# HAT_ID01_OLED.net
KiCad netlist of a schematic drawn in Altium Designer
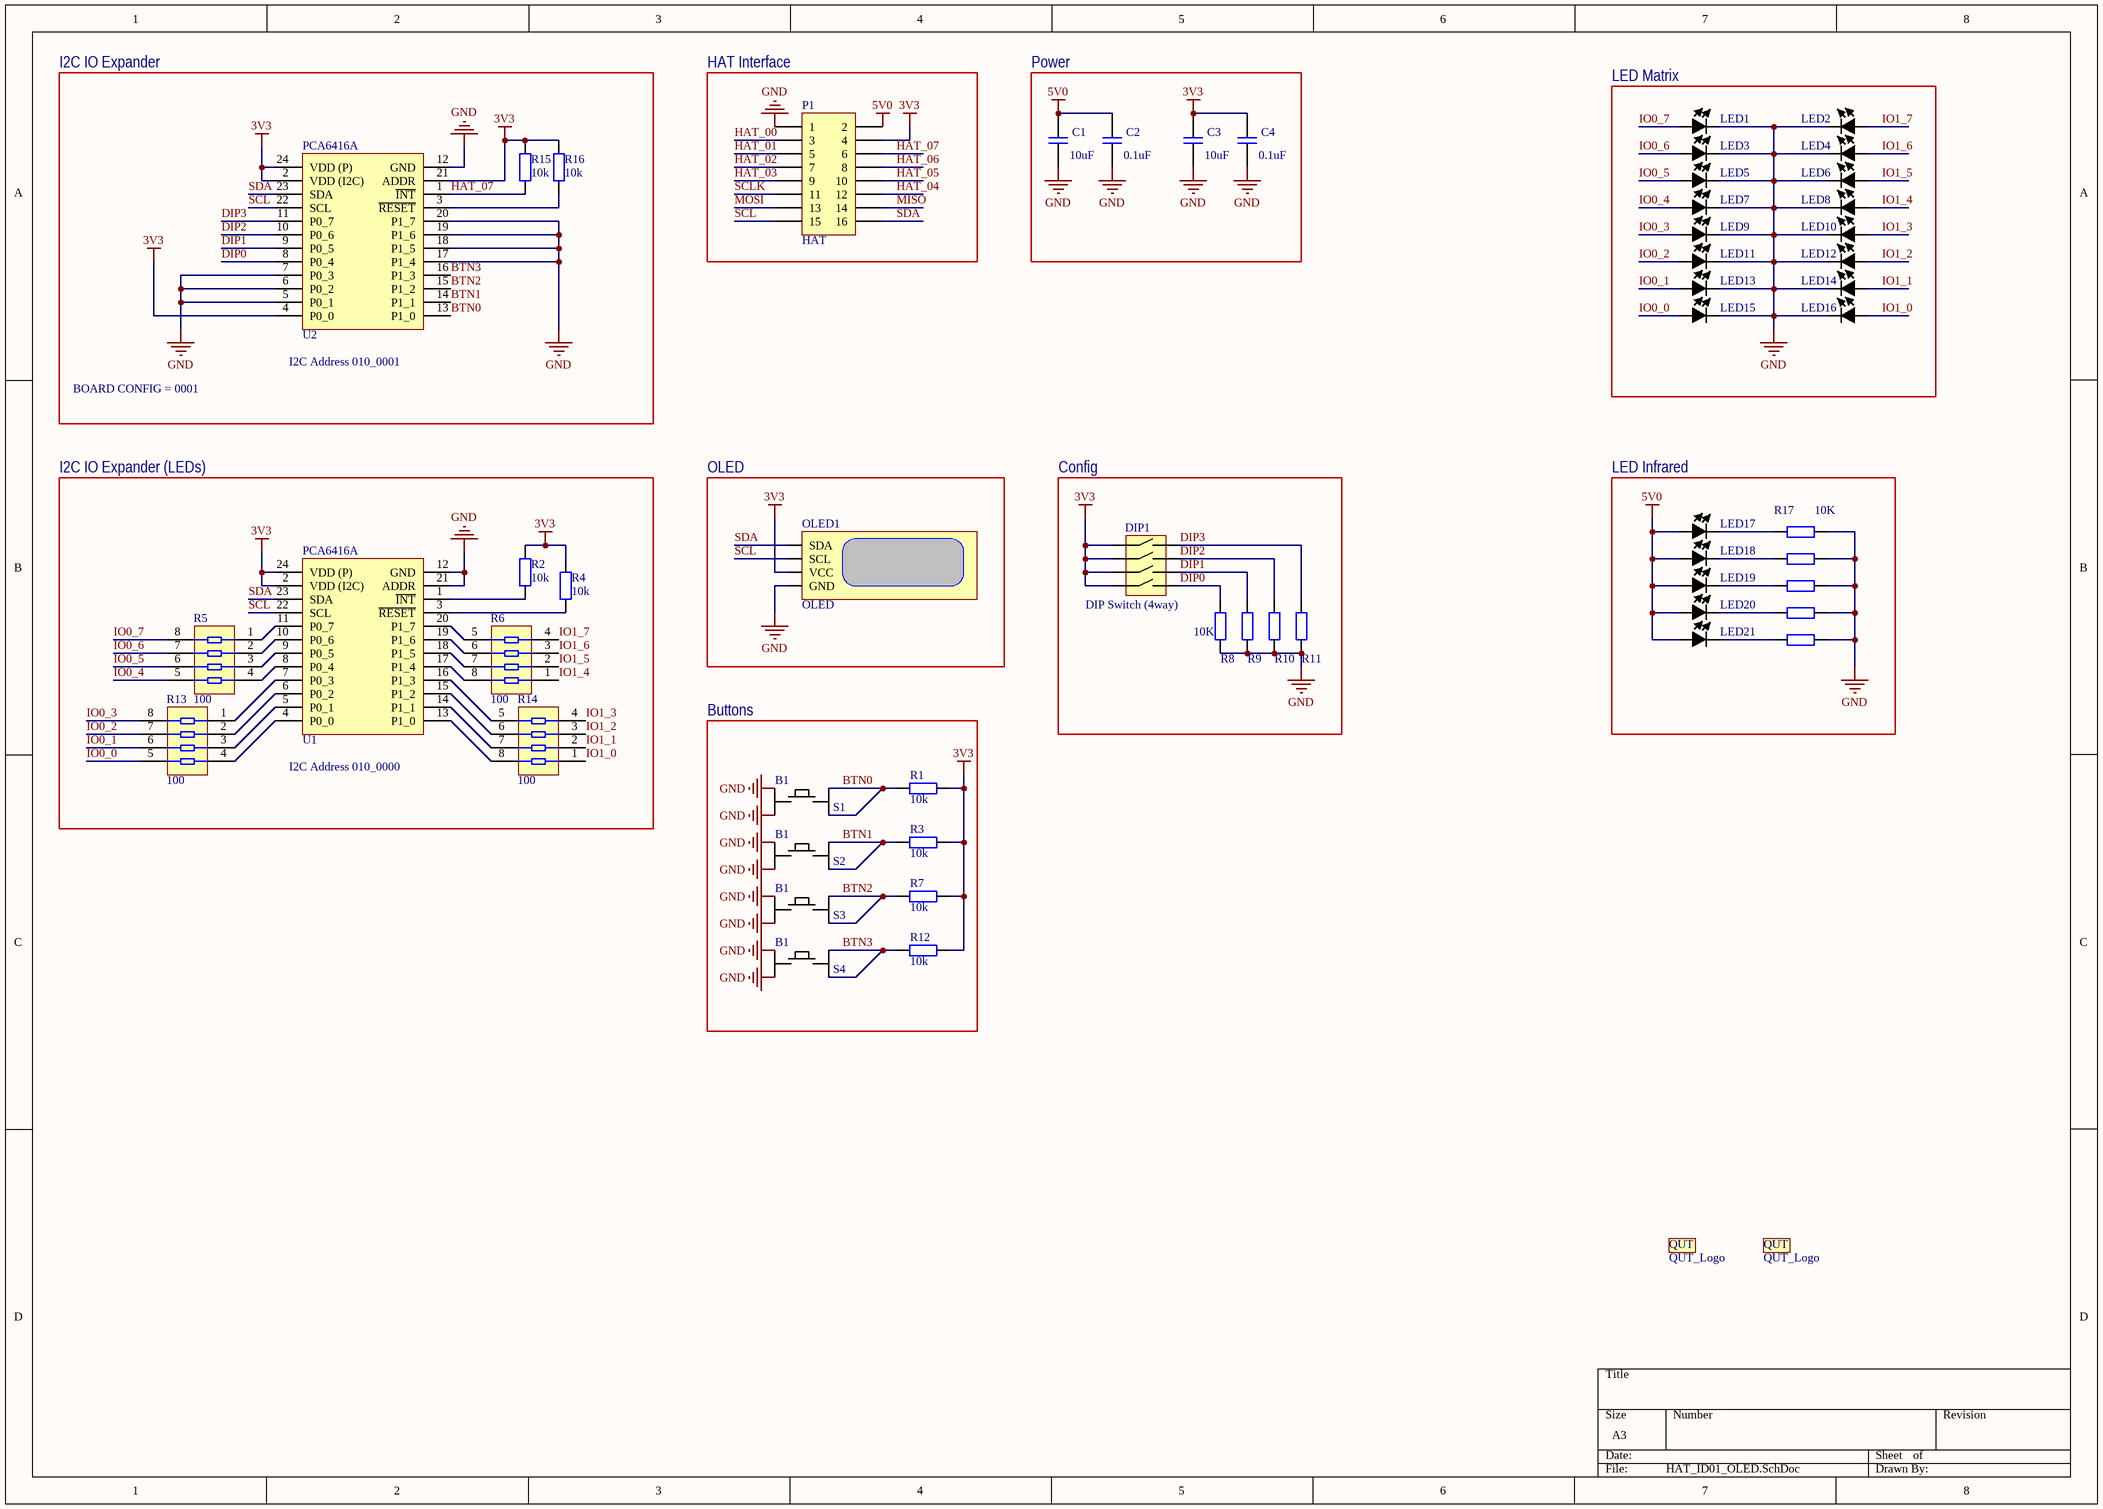
[diagram p0: HAT_ID01_OLED.SchDoc]

(export (version "E")
  (design (tool "Eeschema 10.0.6"))
  (components
    (comp (ref "C1")
      (value "10uF")
      (footprint "C0805")
      (description "Surface mount capacitor")
      (fields (field (name "Comment") "CAP SMD"))
      (libsource (lib "Penguin") (part "CAP SMD"))
    )
    (comp (ref "C2")
      (value "0.1uF")
      (footprint "C0805")
      (description "Surface mount capacitor")
      (fields (field (name "Comment") "CAP SMD"))
      (libsource (lib "Penguin") (part "CAP SMD"))
    )
    (comp (ref "C3")
      (value "10uF")
      (footprint "C0805")
      (description "Surface mount capacitor")
      (fields (field (name "Comment") "CAP SMD"))
      (libsource (lib "Penguin") (part "CAP SMD"))
    )
    (comp (ref "C4")
      (value "0.1uF")
      (footprint "C0805")
      (description "Surface mount capacitor")
      (fields (field (name "Comment") "CAP SMD"))
      (libsource (lib "Penguin") (part "CAP SMD"))
    )
    (comp (ref "DIP1")
      (value "DIP Switch (4way)")
      (footprint "DIP SMD")
      (libsource (lib "QUT") (part "DIP Switch (4way)"))
    )
    (comp (ref "LED1") (value "LED*") (footprint "C0805") (libsource (lib "QUT") (part "LED")))
    (comp (ref "LED2") (value "LED*") (footprint "C0805") (libsource (lib "QUT") (part "LED")))
    (comp (ref "LED3") (value "LED*") (footprint "C0805") (libsource (lib "QUT") (part "LED")))
    (comp (ref "LED4") (value "LED*") (footprint "C0805") (libsource (lib "QUT") (part "LED")))
    (comp (ref "LED5") (value "LED*") (footprint "C0805") (libsource (lib "QUT") (part "LED")))
    (comp (ref "LED6") (value "LED*") (footprint "C0805") (libsource (lib "QUT") (part "LED")))
    (comp (ref "LED7") (value "LED*") (footprint "C0805") (libsource (lib "QUT") (part "LED")))
    (comp (ref "LED8") (value "LED*") (footprint "C0805") (libsource (lib "QUT") (part "LED")))
    (comp (ref "LED9") (value "LED*") (footprint "C0805") (libsource (lib "QUT") (part "LED")))
    (comp (ref "LED10") (value "LED*") (footprint "C0805") (libsource (lib "QUT") (part "LED")))
    (comp (ref "LED11") (value "LED*") (footprint "C0805") (libsource (lib "QUT") (part "LED")))
    (comp (ref "LED12") (value "LED*") (footprint "C0805") (libsource (lib "QUT") (part "LED")))
    (comp (ref "LED13") (value "LED*") (footprint "C0805") (libsource (lib "QUT") (part "LED")))
    (comp (ref "LED14") (value "LED*") (footprint "C0805") (libsource (lib "QUT") (part "LED")))
    (comp (ref "LED15") (value "LED*") (footprint "C0805") (libsource (lib "QUT") (part "LED")))
    (comp (ref "LED16") (value "LED*") (footprint "C0805") (libsource (lib "QUT") (part "LED")))
    (comp (ref "LED17") (value "LED*") (footprint "C0805") (libsource (lib "QUT") (part "LED")))
    (comp (ref "LED18") (value "LED*") (footprint "C0805") (libsource (lib "QUT") (part "LED")))
    (comp (ref "LED19") (value "LED*") (footprint "C0805") (libsource (lib "QUT") (part "LED")))
    (comp (ref "LED20") (value "LED*") (footprint "C0805") (libsource (lib "QUT") (part "LED")))
    (comp (ref "LED21") (value "LED*") (footprint "C0805") (libsource (lib "QUT") (part "LED")))
    (comp (ref "LG1") (value "QUT_Logo") (footprint "QUT_Logo") (libsource (lib "Penguin") (part "QUT_Logo")))
    (comp (ref "LG2") (value "QUT_Logo") (footprint "QUT_Logo") (libsource (lib "Penguin") (part "QUT_Logo")))
    (comp (ref "OLED1") (value "OLED") (footprint "OLED") (libsource (lib "PenguinPi_v2") (part "OLED")))
    (comp (ref "P1")
      (value "HAT")
      (footprint "HDR2X8")
      (description "Header, 8-Pin, Dual row")
      (fields (field (name "PUBLISHER") "Altium Limited"))
      (libsource (lib "Miscellaneous Connectors") (part "Header 8X2"))
    )
    (comp (ref "R1")
      (value "10k")
      (footprint "RESC2012X07N")
      (description "0805 surface mount resistor")
      (fields (field (name "Comment") "RES SMD"))
      (libsource (lib "") (part "RES SMD_1"))
    )
    (comp (ref "R2")
      (value "10k")
      (footprint "RESC2012X07N")
      (description "0805 surface mount resistor")
      (fields (field (name "Comment") "RES SMD"))
      (libsource (lib "Penguin") (part "RES SMD"))
    )
    (comp (ref "R3")
      (value "10k")
      (footprint "RESC2012X07N")
      (description "0805 surface mount resistor")
      (fields (field (name "Comment") "RES SMD"))
      (libsource (lib "") (part "RES SMD_1"))
    )
    (comp (ref "R4")
      (value "10k")
      (footprint "RESC2012X07N")
      (description "0805 surface mount resistor")
      (fields (field (name "Comment") "RES SMD"))
      (libsource (lib "Penguin") (part "RES SMD"))
    )
    (comp (ref "R5")
      (value "100")
      (footprint "CAC-80P319X155-8M")
      (description "Surface mount resistor array")
      (fields (field (name "Comment") "ARRAY"))
      (libsource (lib "Penguin") (part "RES-ARRAY"))
    )
    (comp (ref "R6")
      (value "100")
      (footprint "CAC-80P319X155-8M")
      (description "Surface mount resistor array")
      (fields (field (name "Comment") "ARRAY"))
      (libsource (lib "") (part "RES-ARRAY_1"))
    )
    (comp (ref "R7")
      (value "10k")
      (footprint "RESC2012X07N")
      (description "0805 surface mount resistor")
      (fields (field (name "Comment") "RES SMD"))
      (libsource (lib "") (part "RES SMD_1"))
    )
    (comp (ref "R8")
      (value "10K")
      (footprint "RESC2012X07N")
      (description "0805 surface mount resistor")
      (fields (field (name "Comment") "RES SMD"))
      (libsource (lib "Penguin") (part "RES SMD"))
    )
    (comp (ref "R9")
      (value "RES SMD")
      (footprint "RESC2012X07N")
      (description "0805 surface mount resistor")
      (libsource (lib "Penguin") (part "RES SMD"))
    )
    (comp (ref "R10")
      (value "RES SMD")
      (footprint "RESC2012X07N")
      (description "0805 surface mount resistor")
      (libsource (lib "Penguin") (part "RES SMD"))
    )
    (comp (ref "R11")
      (value "RES SMD")
      (footprint "RESC2012X07N")
      (description "0805 surface mount resistor")
      (libsource (lib "Penguin") (part "RES SMD"))
    )
    (comp (ref "R12")
      (value "10k")
      (footprint "RESC2012X07N")
      (description "0805 surface mount resistor")
      (fields (field (name "Comment") "RES SMD"))
      (libsource (lib "") (part "RES SMD_1"))
    )
    (comp (ref "R13")
      (value "100")
      (footprint "CAC-80P319X155-8M")
      (description "Surface mount resistor array")
      (fields (field (name "Comment") "ARRAY"))
      (libsource (lib "Penguin") (part "RES-ARRAY"))
    )
    (comp (ref "R14")
      (value "100")
      (footprint "CAC-80P319X155-8M")
      (description "Surface mount resistor array")
      (fields (field (name "Comment") "ARRAY"))
      (libsource (lib "") (part "RES-ARRAY_1"))
    )
    (comp (ref "R15")
      (value "10k")
      (footprint "RESC2012X07N")
      (description "0805 surface mount resistor")
      (fields (field (name "Comment") "RES SMD"))
      (libsource (lib "Penguin") (part "RES SMD"))
    )
    (comp (ref "R16")
      (value "10k")
      (footprint "RESC2012X07N")
      (description "0805 surface mount resistor")
      (fields (field (name "Comment") "RES SMD"))
      (libsource (lib "Penguin") (part "RES SMD"))
    )
    (comp (ref "R17")
      (value "10K")
      (footprint "RESC2012X07N")
      (description "0805 surface mount resistor")
      (fields (field (name "Comment") "RES SMD"))
      (libsource (lib "") (part "RES SMD_1"))
    )
    (comp (ref "R18")
      (value "RES SMD")
      (footprint "RESC2012X07N")
      (description "0805 surface mount resistor")
      (libsource (lib "") (part "RES SMD_1"))
    )
    (comp (ref "R19")
      (value "RES SMD")
      (footprint "RESC2012X07N")
      (description "0805 surface mount resistor")
      (libsource (lib "") (part "RES SMD_1"))
    )
    (comp (ref "R20")
      (value "RES SMD")
      (footprint "RESC2012X07N")
      (description "0805 surface mount resistor")
      (libsource (lib "") (part "RES SMD_1"))
    )
    (comp (ref "R21")
      (value "RES SMD")
      (footprint "RESC2012X07N")
      (description "0805 surface mount resistor")
      (libsource (lib "") (part "RES SMD_1"))
    )
    (comp (ref "S1")
      (value "B1")
      (footprint "E-SWITCH-TL3342")
      (description "TL 3342 surface mount pushbutton")
      (libsource (lib "Penguin") (part "E-SWITCH-PUSHBUTTON"))
    )
    (comp (ref "S2")
      (value "B1")
      (footprint "E-SWITCH-TL3342")
      (description "TL 3342 surface mount pushbutton")
      (libsource (lib "Penguin") (part "E-SWITCH-PUSHBUTTON"))
    )
    (comp (ref "S3")
      (value "B1")
      (footprint "E-SWITCH-TL3342")
      (description "TL 3342 surface mount pushbutton")
      (libsource (lib "Penguin") (part "E-SWITCH-PUSHBUTTON"))
    )
    (comp (ref "S4")
      (value "B1")
      (footprint "E-SWITCH-TL3342")
      (description "TL 3342 surface mount pushbutton")
      (libsource (lib "Penguin") (part "E-SWITCH-PUSHBUTTON"))
    )
    (comp (ref "U1")
      (value "PCA6416A")
      (footprint "TSOP65P640X110-24N")
      (description "Low-voltage translating 16-bit I2C I/O port expander")
      (libsource (lib "Penguin") (part "PCA6416APW"))
    )
    (comp (ref "U2")
      (value "PCA6416A")
      (footprint "TSOP65P640X110-24N")
      (description "Low-voltage translating 16-bit I2C I/O port expander")
      (libsource (lib "Penguin") (part "PCA6416APW"))
    )
  )
  (nets
    (net (code "1") (name "/BTN0") (class "Default")
      (node (ref "R1") (pin "2") (pinfunction "2_2") (pintype "passive"))
      (node (ref "S1") (pin "3") (pinfunction "B'_3") (pintype "passive"))
      (node (ref "S1") (pin "4") (pinfunction "B_4") (pintype "passive"))
      (node (ref "U2") (pin "13") (pinfunction "P1_0_13") (pintype "passive"))
    )
    (net (code "2") (name "/BTN1") (class "Default")
      (node (ref "R3") (pin "2") (pinfunction "2_2") (pintype "passive"))
      (node (ref "S2") (pin "3") (pinfunction "B'_3") (pintype "passive"))
      (node (ref "S2") (pin "4") (pinfunction "B_4") (pintype "passive"))
      (node (ref "U2") (pin "14") (pinfunction "P1_1_14") (pintype "passive"))
    )
    (net (code "3") (name "/BTN2") (class "Default")
      (node (ref "R7") (pin "2") (pinfunction "2_2") (pintype "passive"))
      (node (ref "S3") (pin "3") (pinfunction "B'_3") (pintype "passive"))
      (node (ref "S3") (pin "4") (pinfunction "B_4") (pintype "passive"))
      (node (ref "U2") (pin "15") (pinfunction "P1_2_15") (pintype "passive"))
    )
    (net (code "4") (name "/BTN3") (class "Default")
      (node (ref "R12") (pin "2") (pinfunction "2_2") (pintype "passive"))
      (node (ref "S4") (pin "3") (pinfunction "B'_3") (pintype "passive"))
      (node (ref "S4") (pin "4") (pinfunction "B_4") (pintype "passive"))
      (node (ref "U2") (pin "16") (pinfunction "P1_3_16") (pintype "passive"))
    )
    (net (code "5") (name "/DIP0") (class "Default")
      (node (ref "DIP1") (pin "4") (pinfunction "4_4") (pintype "passive"))
      (node (ref "R8") (pin "2") (pinfunction "2_2") (pintype "passive"))
      (node (ref "U2") (pin "8") (pinfunction "P0_4_8") (pintype "passive"))
    )
    (net (code "6") (name "/DIP1") (class "Default")
      (node (ref "DIP1") (pin "5") (pinfunction "5_5") (pintype "passive"))
      (node (ref "R9") (pin "2") (pinfunction "2_2") (pintype "passive"))
      (node (ref "U2") (pin "9") (pinfunction "P0_5_9") (pintype "passive"))
    )
    (net (code "7") (name "/DIP2") (class "Default")
      (node (ref "DIP1") (pin "6") (pinfunction "6_6") (pintype "passive"))
      (node (ref "R10") (pin "2") (pinfunction "2_2") (pintype "passive"))
      (node (ref "U2") (pin "10") (pinfunction "P0_6_10") (pintype "passive"))
    )
    (net (code "8") (name "/DIP3") (class "Default")
      (node (ref "DIP1") (pin "7") (pinfunction "7_7") (pintype "passive"))
      (node (ref "R11") (pin "2") (pinfunction "2_2") (pintype "passive"))
      (node (ref "U2") (pin "11") (pinfunction "P0_7_11") (pintype "passive"))
    )
    (net (code "9") (name "/HAT_00") (class "Default")
      (node (ref "P1") (pin "3") (pinfunction "3_3") (pintype "passive"))
    )
    (net (code "10") (name "/HAT_01") (class "Default")
      (node (ref "P1") (pin "5") (pinfunction "5_5") (pintype "passive"))
    )
    (net (code "11") (name "/HAT_02") (class "Default")
      (node (ref "P1") (pin "7") (pinfunction "7_7") (pintype "passive"))
    )
    (net (code "12") (name "/HAT_03") (class "Default")
      (node (ref "P1") (pin "9") (pinfunction "9_9") (pintype "passive"))
    )
    (net (code "13") (name "/HAT_04") (class "Default")
      (node (ref "P1") (pin "12") (pinfunction "12_12") (pintype "passive"))
    )
    (net (code "14") (name "/HAT_05") (class "Default")
      (node (ref "P1") (pin "10") (pinfunction "10_10") (pintype "passive"))
    )
    (net (code "15") (name "/HAT_06") (class "Default")
      (node (ref "P1") (pin "8") (pinfunction "8_8") (pintype "passive"))
    )
    (net (code "16") (name "/HAT_07") (class "Default")
      (node (ref "P1") (pin "6") (pinfunction "6_6") (pintype "passive"))
      (node (ref "R15") (pin "1") (pinfunction "1_1") (pintype "passive"))
      (node (ref "U2") (pin "1") (pinfunction "~{INT}_1") (pintype "passive"))
    )
    (net (code "17") (name "/IO0_0") (class "Default")
      (node (ref "LED15") (pin "1") (pinfunction "1_1") (pintype "passive"))
      (node (ref "R13") (pin "5") (pintype "passive"))
    )
    (net (code "18") (name "/IO0_1") (class "Default")
      (node (ref "LED13") (pin "1") (pinfunction "1_1") (pintype "passive"))
      (node (ref "R13") (pin "6") (pintype "passive"))
    )
    (net (code "19") (name "/IO0_2") (class "Default")
      (node (ref "LED11") (pin "1") (pinfunction "1_1") (pintype "passive"))
      (node (ref "R13") (pin "7") (pintype "passive"))
    )
    (net (code "20") (name "/IO0_3") (class "Default")
      (node (ref "LED9") (pin "1") (pinfunction "1_1") (pintype "passive"))
      (node (ref "R13") (pin "8") (pintype "passive"))
    )
    (net (code "21") (name "/IO0_4") (class "Default")
      (node (ref "LED7") (pin "1") (pinfunction "1_1") (pintype "passive"))
      (node (ref "R5") (pin "5") (pintype "passive"))
    )
    (net (code "22") (name "/IO0_5") (class "Default")
      (node (ref "LED5") (pin "1") (pinfunction "1_1") (pintype "passive"))
      (node (ref "R5") (pin "6") (pintype "passive"))
    )
    (net (code "23") (name "/IO0_6") (class "Default")
      (node (ref "LED3") (pin "1") (pinfunction "1_1") (pintype "passive"))
      (node (ref "R5") (pin "7") (pintype "passive"))
    )
    (net (code "24") (name "/IO0_7") (class "Default")
      (node (ref "LED1") (pin "1") (pinfunction "1_1") (pintype "passive"))
      (node (ref "R5") (pin "8") (pintype "passive"))
    )
    (net (code "25") (name "/IO1_0") (class "Default")
      (node (ref "LED16") (pin "1") (pinfunction "1_1") (pintype "passive"))
      (node (ref "R14") (pin "1") (pintype "passive"))
    )
    (net (code "26") (name "/IO1_1") (class "Default")
      (node (ref "LED14") (pin "1") (pinfunction "1_1") (pintype "passive"))
      (node (ref "R14") (pin "2") (pintype "passive"))
    )
    (net (code "27") (name "/IO1_2") (class "Default")
      (node (ref "LED12") (pin "1") (pinfunction "1_1") (pintype "passive"))
      (node (ref "R14") (pin "3") (pintype "passive"))
    )
    (net (code "28") (name "/IO1_3") (class "Default")
      (node (ref "LED10") (pin "1") (pinfunction "1_1") (pintype "passive"))
      (node (ref "R14") (pin "4") (pintype "passive"))
    )
    (net (code "29") (name "/IO1_4") (class "Default")
      (node (ref "LED8") (pin "1") (pinfunction "1_1") (pintype "passive"))
      (node (ref "R6") (pin "1") (pintype "passive"))
    )
    (net (code "30") (name "/IO1_5") (class "Default")
      (node (ref "LED6") (pin "1") (pinfunction "1_1") (pintype "passive"))
      (node (ref "R6") (pin "2") (pintype "passive"))
    )
    (net (code "31") (name "/IO1_6") (class "Default")
      (node (ref "LED4") (pin "1") (pinfunction "1_1") (pintype "passive"))
      (node (ref "R6") (pin "3") (pintype "passive"))
    )
    (net (code "32") (name "/IO1_7") (class "Default")
      (node (ref "LED2") (pin "1") (pinfunction "1_1") (pintype "passive"))
      (node (ref "R6") (pin "4") (pintype "passive"))
    )
    (net (code "33") (name "/MISO") (class "Default")
      (node (ref "P1") (pin "14") (pinfunction "14_14") (pintype "passive"))
    )
    (net (code "34") (name "/MOSI") (class "Default")
      (node (ref "P1") (pin "13") (pinfunction "13_13") (pintype "passive"))
    )
    (net (code "35") (name "/SCL") (class "Default")
      (node (ref "OLED1") (pin "3") (pinfunction "SCL_3") (pintype "passive"))
      (node (ref "P1") (pin "15") (pinfunction "15_15") (pintype "passive"))
      (node (ref "U1") (pin "22") (pinfunction "SCL_22") (pintype "passive"))
      (node (ref "U2") (pin "22") (pinfunction "SCL_22") (pintype "passive"))
    )
    (net (code "36") (name "/SCLK") (class "Default")
      (node (ref "P1") (pin "11") (pinfunction "11_11") (pintype "passive"))
    )
    (net (code "37") (name "/SDA") (class "Default")
      (node (ref "OLED1") (pin "4") (pinfunction "SDA_4") (pintype "passive"))
      (node (ref "P1") (pin "16") (pinfunction "16_16") (pintype "passive"))
      (node (ref "U1") (pin "23") (pinfunction "SDA_23") (pintype "passive"))
      (node (ref "U2") (pin "23") (pinfunction "SDA_23") (pintype "passive"))
    )
    (net (code "38") (name "3V3") (class "Default")
      (node (ref "C3") (pin "2") (pinfunction "K_2") (pintype "passive"))
      (node (ref "C4") (pin "2") (pinfunction "K_2") (pintype "passive"))
      (node (ref "DIP1") (pin "0") (pinfunction "0_0") (pintype "passive"))
      (node (ref "DIP1") (pin "1") (pinfunction "1_1") (pintype "passive"))
      (node (ref "DIP1") (pin "2") (pinfunction "2_2") (pintype "passive"))
      (node (ref "DIP1") (pin "3") (pinfunction "3_3") (pintype "passive"))
      (node (ref "OLED1") (pin "2") (pinfunction "VCC_2") (pintype "passive"))
      (node (ref "P1") (pin "4") (pinfunction "4_4") (pintype "passive"))
      (node (ref "R1") (pin "1") (pinfunction "1_1") (pintype "passive"))
      (node (ref "R12") (pin "1") (pinfunction "1_1") (pintype "passive"))
      (node (ref "R15") (pin "2") (pinfunction "2_2") (pintype "passive"))
      (node (ref "R16") (pin "2") (pinfunction "2_2") (pintype "passive"))
      (node (ref "R2") (pin "2") (pinfunction "2_2") (pintype "passive"))
      (node (ref "R3") (pin "1") (pinfunction "1_1") (pintype "passive"))
      (node (ref "R4") (pin "2") (pinfunction "2_2") (pintype "passive"))
      (node (ref "R7") (pin "1") (pinfunction "1_1") (pintype "passive"))
      (node (ref "U1") (pin "2") (pinfunction "VDD_(I2C)_2") (pintype "passive"))
      (node (ref "U1") (pin "24") (pinfunction "VDD_(P)_24") (pintype "passive"))
      (node (ref "U2") (pin "2") (pinfunction "VDD_(I2C)_2") (pintype "passive"))
      (node (ref "U2") (pin "21") (pinfunction "ADDR_21") (pintype "passive"))
      (node (ref "U2") (pin "24") (pinfunction "VDD_(P)_24") (pintype "passive"))
      (node (ref "U2") (pin "4") (pinfunction "P0_0_4") (pintype "passive"))
    )
    (net (code "39") (name "5V0") (class "Default")
      (node (ref "C1") (pin "2") (pinfunction "K_2") (pintype "passive"))
      (node (ref "C2") (pin "2") (pinfunction "K_2") (pintype "passive"))
      (node (ref "LED17") (pin "1") (pinfunction "1_1") (pintype "passive"))
      (node (ref "LED18") (pin "1") (pinfunction "1_1") (pintype "passive"))
      (node (ref "LED19") (pin "1") (pinfunction "1_1") (pintype "passive"))
      (node (ref "LED20") (pin "1") (pinfunction "1_1") (pintype "passive"))
      (node (ref "LED21") (pin "1") (pinfunction "1_1") (pintype "passive"))
      (node (ref "P1") (pin "2") (pinfunction "2_2") (pintype "passive"))
    )
    (net (code "40") (name "GND") (class "Default")
      (node (ref "C1") (pin "1") (pinfunction "A_1") (pintype "passive"))
      (node (ref "C2") (pin "1") (pinfunction "A_1") (pintype "passive"))
      (node (ref "C3") (pin "1") (pinfunction "A_1") (pintype "passive"))
      (node (ref "C4") (pin "1") (pinfunction "A_1") (pintype "passive"))
      (node (ref "LED1") (pin "2") (pinfunction "2_2") (pintype "passive"))
      (node (ref "LED10") (pin "2") (pinfunction "2_2") (pintype "passive"))
      (node (ref "LED11") (pin "2") (pinfunction "2_2") (pintype "passive"))
      (node (ref "LED12") (pin "2") (pinfunction "2_2") (pintype "passive"))
      (node (ref "LED13") (pin "2") (pinfunction "2_2") (pintype "passive"))
      (node (ref "LED14") (pin "2") (pinfunction "2_2") (pintype "passive"))
      (node (ref "LED15") (pin "2") (pinfunction "2_2") (pintype "passive"))
      (node (ref "LED16") (pin "2") (pinfunction "2_2") (pintype "passive"))
      (node (ref "LED2") (pin "2") (pinfunction "2_2") (pintype "passive"))
      (node (ref "LED3") (pin "2") (pinfunction "2_2") (pintype "passive"))
      (node (ref "LED4") (pin "2") (pinfunction "2_2") (pintype "passive"))
      (node (ref "LED5") (pin "2") (pinfunction "2_2") (pintype "passive"))
      (node (ref "LED6") (pin "2") (pinfunction "2_2") (pintype "passive"))
      (node (ref "LED7") (pin "2") (pinfunction "2_2") (pintype "passive"))
      (node (ref "LED8") (pin "2") (pinfunction "2_2") (pintype "passive"))
      (node (ref "LED9") (pin "2") (pinfunction "2_2") (pintype "passive"))
      (node (ref "OLED1") (pin "1") (pinfunction "GND_1") (pintype "passive"))
      (node (ref "P1") (pin "1") (pinfunction "1_1") (pintype "passive"))
      (node (ref "R10") (pin "1") (pinfunction "1_1") (pintype "passive"))
      (node (ref "R11") (pin "1") (pinfunction "1_1") (pintype "passive"))
      (node (ref "R17") (pin "1") (pinfunction "1_1") (pintype "passive"))
      (node (ref "R18") (pin "1") (pinfunction "1_1") (pintype "passive"))
      (node (ref "R19") (pin "1") (pinfunction "1_1") (pintype "passive"))
      (node (ref "R20") (pin "1") (pinfunction "1_1") (pintype "passive"))
      (node (ref "R21") (pin "1") (pinfunction "1_1") (pintype "passive"))
      (node (ref "R8") (pin "1") (pinfunction "1_1") (pintype "passive"))
      (node (ref "R9") (pin "1") (pinfunction "1_1") (pintype "passive"))
      (node (ref "S1") (pin "1") (pinfunction "A_1") (pintype "passive"))
      (node (ref "S1") (pin "2") (pinfunction "A'_2") (pintype "passive"))
      (node (ref "S2") (pin "1") (pinfunction "A_1") (pintype "passive"))
      (node (ref "S2") (pin "2") (pinfunction "A'_2") (pintype "passive"))
      (node (ref "S3") (pin "1") (pinfunction "A_1") (pintype "passive"))
      (node (ref "S3") (pin "2") (pinfunction "A'_2") (pintype "passive"))
      (node (ref "S4") (pin "1") (pinfunction "A_1") (pintype "passive"))
      (node (ref "S4") (pin "2") (pinfunction "A'_2") (pintype "passive"))
      (node (ref "U1") (pin "12") (pinfunction "GND_12") (pintype "passive"))
      (node (ref "U1") (pin "21") (pinfunction "ADDR_21") (pintype "passive"))
      (node (ref "U2") (pin "12") (pinfunction "GND_12") (pintype "passive"))
      (node (ref "U2") (pin "17") (pinfunction "P1_4_17") (pintype "passive"))
      (node (ref "U2") (pin "18") (pinfunction "P1_5_18") (pintype "passive"))
      (node (ref "U2") (pin "19") (pinfunction "P1_6_19") (pintype "passive"))
      (node (ref "U2") (pin "20") (pinfunction "P1_7_20") (pintype "passive"))
      (node (ref "U2") (pin "5") (pinfunction "P0_1_5") (pintype "passive"))
      (node (ref "U2") (pin "6") (pinfunction "P0_2_6") (pintype "passive"))
      (node (ref "U2") (pin "7") (pinfunction "P0_3_7") (pintype "passive"))
    )
    (net (code "41") (name "Net-(LED17-Pad2)") (class "Default")
      (node (ref "LED17") (pin "2") (pinfunction "2_2") (pintype "passive"))
      (node (ref "R17") (pin "2") (pinfunction "2_2") (pintype "passive"))
    )
    (net (code "42") (name "Net-(LED18-Pad2)") (class "Default")
      (node (ref "LED18") (pin "2") (pinfunction "2_2") (pintype "passive"))
      (node (ref "R18") (pin "2") (pinfunction "2_2") (pintype "passive"))
    )
    (net (code "43") (name "Net-(LED19-Pad2)") (class "Default")
      (node (ref "LED19") (pin "2") (pinfunction "2_2") (pintype "passive"))
      (node (ref "R19") (pin "2") (pinfunction "2_2") (pintype "passive"))
    )
    (net (code "44") (name "Net-(LED20-Pad2)") (class "Default")
      (node (ref "LED20") (pin "2") (pinfunction "2_2") (pintype "passive"))
      (node (ref "R20") (pin "2") (pinfunction "2_2") (pintype "passive"))
    )
    (net (code "45") (name "Net-(LED21-Pad2)") (class "Default")
      (node (ref "LED21") (pin "2") (pinfunction "2_2") (pintype "passive"))
      (node (ref "R21") (pin "2") (pinfunction "2_2") (pintype "passive"))
    )
    (net (code "46") (name "Net-(U1-P0_0)") (class "Default")
      (node (ref "R13") (pin "4") (pintype "passive"))
      (node (ref "U1") (pin "4") (pinfunction "P0_0_4") (pintype "passive"))
    )
    (net (code "47") (name "Net-(U1-P0_1)") (class "Default")
      (node (ref "R13") (pin "3") (pintype "passive"))
      (node (ref "U1") (pin "5") (pinfunction "P0_1_5") (pintype "passive"))
    )
    (net (code "48") (name "Net-(U1-P0_2)") (class "Default")
      (node (ref "R13") (pin "2") (pintype "passive"))
      (node (ref "U1") (pin "6") (pinfunction "P0_2_6") (pintype "passive"))
    )
    (net (code "49") (name "Net-(U1-P0_3)") (class "Default")
      (node (ref "R13") (pin "1") (pintype "passive"))
      (node (ref "U1") (pin "7") (pinfunction "P0_3_7") (pintype "passive"))
    )
    (net (code "50") (name "Net-(U1-P0_4)") (class "Default")
      (node (ref "R5") (pin "4") (pintype "passive"))
      (node (ref "U1") (pin "8") (pinfunction "P0_4_8") (pintype "passive"))
    )
    (net (code "51") (name "Net-(U1-P0_5)") (class "Default")
      (node (ref "R5") (pin "3") (pintype "passive"))
      (node (ref "U1") (pin "9") (pinfunction "P0_5_9") (pintype "passive"))
    )
    (net (code "52") (name "Net-(U1-P0_6)") (class "Default")
      (node (ref "R5") (pin "2") (pintype "passive"))
      (node (ref "U1") (pin "10") (pinfunction "P0_6_10") (pintype "passive"))
    )
    (net (code "53") (name "Net-(U1-P0_7)") (class "Default")
      (node (ref "R5") (pin "1") (pintype "passive"))
      (node (ref "U1") (pin "11") (pinfunction "P0_7_11") (pintype "passive"))
    )
    (net (code "54") (name "Net-(U1-P1_0)") (class "Default")
      (node (ref "R14") (pin "8") (pintype "passive"))
      (node (ref "U1") (pin "13") (pinfunction "P1_0_13") (pintype "passive"))
    )
    (net (code "55") (name "Net-(U1-P1_1)") (class "Default")
      (node (ref "R14") (pin "7") (pintype "passive"))
      (node (ref "U1") (pin "14") (pinfunction "P1_1_14") (pintype "passive"))
    )
    (net (code "56") (name "Net-(U1-P1_2)") (class "Default")
      (node (ref "R14") (pin "6") (pintype "passive"))
      (node (ref "U1") (pin "15") (pinfunction "P1_2_15") (pintype "passive"))
    )
    (net (code "57") (name "Net-(U1-P1_3)") (class "Default")
      (node (ref "R14") (pin "5") (pintype "passive"))
      (node (ref "U1") (pin "16") (pinfunction "P1_3_16") (pintype "passive"))
    )
    (net (code "58") (name "Net-(U1-P1_4)") (class "Default")
      (node (ref "R6") (pin "8") (pintype "passive"))
      (node (ref "U1") (pin "17") (pinfunction "P1_4_17") (pintype "passive"))
    )
    (net (code "59") (name "Net-(U1-P1_5)") (class "Default")
      (node (ref "R6") (pin "7") (pintype "passive"))
      (node (ref "U1") (pin "18") (pinfunction "P1_5_18") (pintype "passive"))
    )
    (net (code "60") (name "Net-(U1-P1_6)") (class "Default")
      (node (ref "R6") (pin "6") (pintype "passive"))
      (node (ref "U1") (pin "19") (pinfunction "P1_6_19") (pintype "passive"))
    )
    (net (code "61") (name "Net-(U1-P1_7)") (class "Default")
      (node (ref "R6") (pin "5") (pintype "passive"))
      (node (ref "U1") (pin "20") (pinfunction "P1_7_20") (pintype "passive"))
    )
    (net (code "62") (name "Net-(U1-~{INT})") (class "Default")
      (node (ref "R2") (pin "1") (pinfunction "1_1") (pintype "passive"))
      (node (ref "U1") (pin "1") (pinfunction "~{INT}_1") (pintype "passive"))
    )
    (net (code "63") (name "Net-(U1-~{RESET})") (class "Default")
      (node (ref "R4") (pin "1") (pinfunction "1_1") (pintype "passive"))
      (node (ref "U1") (pin "3") (pinfunction "~{RESET}_3") (pintype "passive"))
    )
    (net (code "64") (name "Net-(U2-~{RESET})") (class "Default")
      (node (ref "R16") (pin "1") (pinfunction "1_1") (pintype "passive"))
      (node (ref "U2") (pin "3") (pinfunction "~{RESET}_3") (pintype "passive"))
    )
  )
)
